# serial_extender.net
KiCad netlist of a schematic drawn in EAGLE
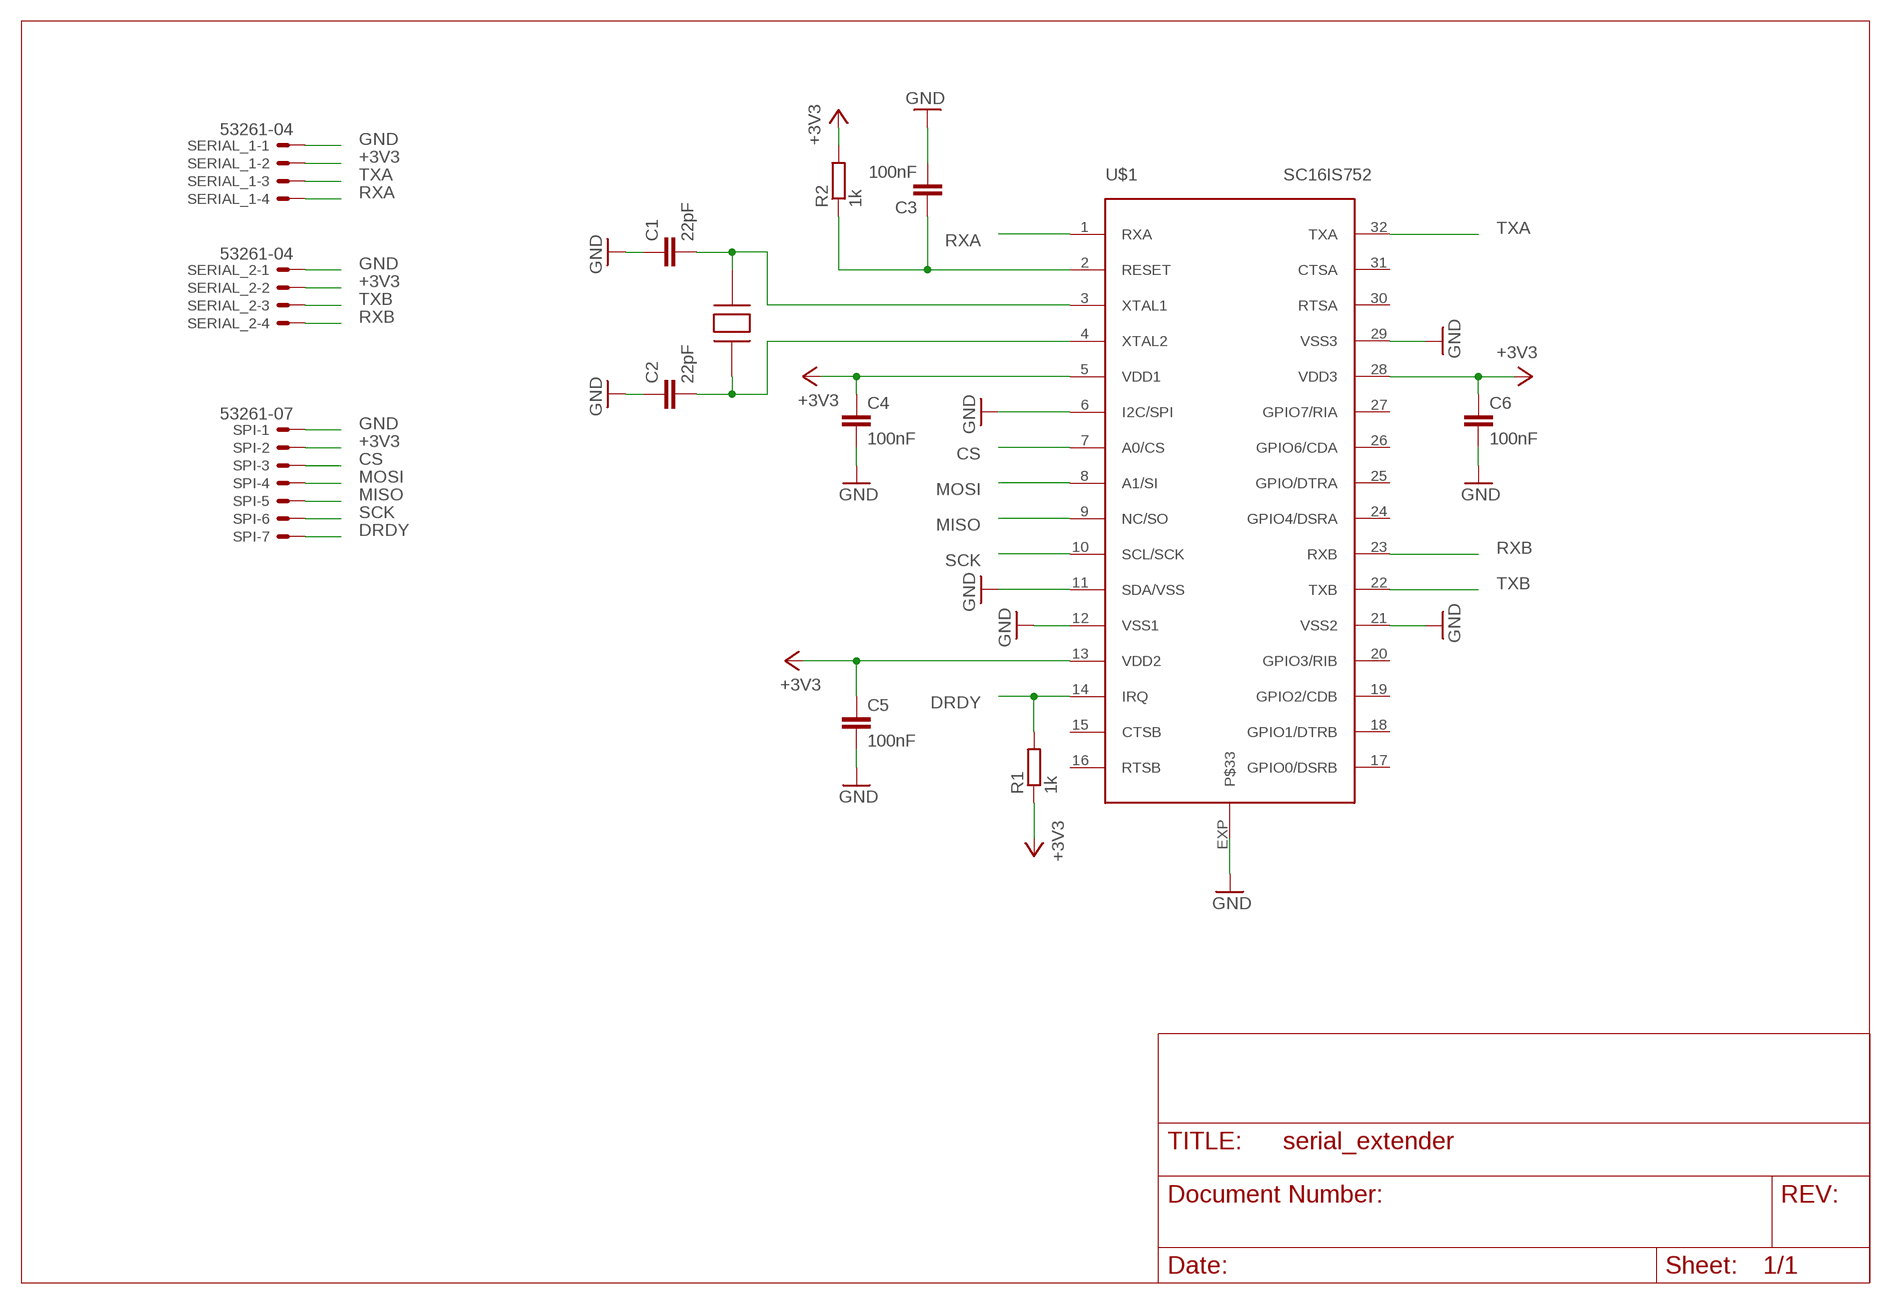
[diagram p0: schematic, sheet 1]

(export (version "E")
  (design (tool "Eeschema 10.0.6"))
  (components
    (comp (ref "C1")
      (value "22pF")
      (footprint "eagle-import:C0603K")
      (libsource (lib "eagle-import") (part "C-EUC0603K"))
    )
    (comp (ref "C2")
      (value "22pF")
      (footprint "eagle-import:C0603K")
      (libsource (lib "eagle-import") (part "C-EUC0603K"))
    )
    (comp (ref "C3")
      (value "100nF")
      (footprint "eagle-import:C0603K")
      (libsource (lib "eagle-import") (part "C-EUC0603K"))
    )
    (comp (ref "C4")
      (value "100nF")
      (footprint "eagle-import:C0603K")
      (libsource (lib "eagle-import") (part "C-EUC0603K"))
    )
    (comp (ref "C5")
      (value "100nF")
      (footprint "eagle-import:C0603K")
      (libsource (lib "eagle-import") (part "C-EUC0603K"))
    )
    (comp (ref "C6")
      (value "100nF")
      (footprint "eagle-import:C0603K")
      (libsource (lib "eagle-import") (part "C-EUC0603K"))
    )
    (comp (ref "R1")
      (value "1k")
      (footprint "eagle-import:R0603")
      (libsource (lib "eagle-import") (part "R-EU_R0603"))
    )
    (comp (ref "R2")
      (value "1k")
      (footprint "eagle-import:R0603")
      (libsource (lib "eagle-import") (part "R-EU_R0603"))
    )
    (comp (ref "SERIAL_1")
      (value "53261-04")
      (footprint "eagle-import:53261-04")
      (libsource (lib "eagle-import") (part "53?-04261"))
    )
    (comp (ref "SERIAL_2")
      (value "53261-04")
      (footprint "eagle-import:53261-04")
      (libsource (lib "eagle-import") (part "53?-04261"))
    )
    (comp (ref "SPI")
      (value "53261-07")
      (footprint "eagle-import:53261-07")
      (libsource (lib "eagle-import") (part "53?-07261"))
    )
    (comp (ref "U$1")
      (value "SC16IS752")
      (footprint "eagle-import:HVQFN32")
      (libsource (lib "eagle-import") (part "SC16IS752"))
    )
    (comp (ref "U$2")
      (value "CRYSTAL_CTS")
      (footprint "eagle-import:CTS_CRYSTAL")
      (libsource (lib "eagle-import") (part "CRYSTAL_CTS"))
    )
  )
  (nets
    (net (code "1") (name "+3V3") (class "Default")
      (node (ref "C4") (pin "1") (pinfunction "1_1") (pintype "passive"))
      (node (ref "C5") (pin "1") (pinfunction "1_1") (pintype "passive"))
      (node (ref "C6") (pin "1") (pinfunction "1_1") (pintype "passive"))
      (node (ref "R1") (pin "1") (pinfunction "1_1") (pintype "passive"))
      (node (ref "R2") (pin "2") (pinfunction "2_2") (pintype "passive"))
      (node (ref "SERIAL_1") (pin "2") (pinfunction "S_2") (pintype "passive"))
      (node (ref "SERIAL_2") (pin "2") (pinfunction "S_2") (pintype "passive"))
      (node (ref "SPI") (pin "2") (pinfunction "S_2") (pintype "passive"))
      (node (ref "U$1") (pin "13") (pinfunction "VDD2_13") (pintype "bidirectional"))
      (node (ref "U$1") (pin "28") (pinfunction "VDD3_28") (pintype "bidirectional"))
      (node (ref "U$1") (pin "5") (pinfunction "VDD1_5") (pintype "bidirectional"))
    )
    (net (code "2") (name "/CS") (class "Default")
      (node (ref "SPI") (pin "3") (pinfunction "S_3") (pintype "passive"))
      (node (ref "U$1") (pin "7") (pinfunction "A0/CS_7") (pintype "bidirectional"))
    )
    (net (code "3") (name "/DRDY") (class "Default")
      (node (ref "R1") (pin "2") (pinfunction "2_2") (pintype "passive"))
      (node (ref "SPI") (pin "7") (pinfunction "S_7") (pintype "passive"))
      (node (ref "U$1") (pin "14") (pinfunction "IRQ_14") (pintype "bidirectional"))
    )
    (net (code "4") (name "/MISO") (class "Default")
      (node (ref "SPI") (pin "5") (pinfunction "S_5") (pintype "passive"))
      (node (ref "U$1") (pin "9") (pinfunction "NC/SO_9") (pintype "bidirectional"))
    )
    (net (code "5") (name "/MOSI") (class "Default")
      (node (ref "SPI") (pin "4") (pinfunction "S_4") (pintype "passive"))
      (node (ref "U$1") (pin "8") (pinfunction "A1/SI_8") (pintype "bidirectional"))
    )
    (net (code "6") (name "/RXA") (class "Default")
      (node (ref "SERIAL_1") (pin "4") (pinfunction "S_4") (pintype "passive"))
      (node (ref "U$1") (pin "1") (pinfunction "RXA_1") (pintype "bidirectional"))
    )
    (net (code "7") (name "/RXB") (class "Default")
      (node (ref "SERIAL_2") (pin "4") (pinfunction "S_4") (pintype "passive"))
      (node (ref "U$1") (pin "23") (pinfunction "RXB_23") (pintype "bidirectional"))
    )
    (net (code "8") (name "/SCK") (class "Default")
      (node (ref "SPI") (pin "6") (pinfunction "S_6") (pintype "passive"))
      (node (ref "U$1") (pin "10") (pinfunction "SCL/SCK_10") (pintype "bidirectional"))
    )
    (net (code "9") (name "/TXA") (class "Default")
      (node (ref "SERIAL_1") (pin "3") (pinfunction "S_3") (pintype "passive"))
      (node (ref "U$1") (pin "32") (pinfunction "TXA_32") (pintype "bidirectional"))
    )
    (net (code "10") (name "/TXB") (class "Default")
      (node (ref "SERIAL_2") (pin "3") (pinfunction "S_3") (pintype "passive"))
      (node (ref "U$1") (pin "22") (pinfunction "TXB_22") (pintype "bidirectional"))
    )
    (net (code "11") (name "GND") (class "Default")
      (node (ref "C1") (pin "1") (pinfunction "1_1") (pintype "passive"))
      (node (ref "C2") (pin "1") (pinfunction "1_1") (pintype "passive"))
      (node (ref "C3") (pin "2") (pinfunction "2_2") (pintype "passive"))
      (node (ref "C4") (pin "2") (pinfunction "2_2") (pintype "passive"))
      (node (ref "C5") (pin "2") (pinfunction "2_2") (pintype "passive"))
      (node (ref "C6") (pin "2") (pinfunction "2_2") (pintype "passive"))
      (node (ref "SERIAL_1") (pin "1") (pinfunction "S_1") (pintype "passive"))
      (node (ref "SERIAL_2") (pin "1") (pinfunction "S_1") (pintype "passive"))
      (node (ref "SPI") (pin "1") (pinfunction "S_1") (pintype "passive"))
      (node (ref "U$1") (pin "11") (pinfunction "SDA/VSS_11") (pintype "bidirectional"))
      (node (ref "U$1") (pin "12") (pinfunction "VSS1_12") (pintype "bidirectional"))
      (node (ref "U$1") (pin "21") (pinfunction "VSS2_21") (pintype "bidirectional"))
      (node (ref "U$1") (pin "29") (pinfunction "VSS3_29") (pintype "bidirectional"))
      (node (ref "U$1") (pin "6") (pinfunction "I2C/SPI_6") (pintype "bidirectional"))
      (node (ref "U$1") (pin "EXP") (pinfunction "P$33_EXP") (pintype "bidirectional"))
    )
    (net (code "12") (name "Net-(U$1-RESET)") (class "Default")
      (node (ref "C3") (pin "1") (pinfunction "1_1") (pintype "passive"))
      (node (ref "R2") (pin "1") (pinfunction "1_1") (pintype "passive"))
      (node (ref "U$1") (pin "2") (pinfunction "RESET_2") (pintype "bidirectional"))
    )
    (net (code "13") (name "Net-(U$1-XTAL1)") (class "Default")
      (node (ref "C1") (pin "2") (pinfunction "2_2") (pintype "passive"))
      (node (ref "U$1") (pin "3") (pinfunction "XTAL1_3") (pintype "bidirectional"))
      (node (ref "U$2") (pin "P$3") (pinfunction "P$2_P$3") (pintype "bidirectional"))
    )
    (net (code "14") (name "Net-(U$1-XTAL2)") (class "Default")
      (node (ref "C2") (pin "2") (pinfunction "2_2") (pintype "passive"))
      (node (ref "U$1") (pin "4") (pinfunction "XTAL2_4") (pintype "bidirectional"))
      (node (ref "U$2") (pin "P$1") (pinfunction "P$1_P$1") (pintype "bidirectional"))
    )
    (net (code "15") (name "unconnected-(U$1-CTSA-Pad31)") (class "Default")
      (node (ref "U$1") (pin "31") (pinfunction "CTSA_31") (pintype "bidirectional"))
    )
    (net (code "16") (name "unconnected-(U$1-CTSB-Pad15)") (class "Default")
      (node (ref "U$1") (pin "15") (pinfunction "CTSB_15") (pintype "bidirectional"))
    )
    (net (code "17") (name "unconnected-(U$1-GPIO0{slash}DSRB-Pad17)") (class "Default")
      (node (ref "U$1") (pin "17") (pinfunction "GPIO0/DSRB_17") (pintype "bidirectional"))
    )
    (net (code "18") (name "unconnected-(U$1-GPIO1{slash}DTRB-Pad18)") (class "Default")
      (node (ref "U$1") (pin "18") (pinfunction "GPIO1/DTRB_18") (pintype "bidirectional"))
    )
    (net (code "19") (name "unconnected-(U$1-GPIO2{slash}CDB-Pad19)") (class "Default")
      (node (ref "U$1") (pin "19") (pinfunction "GPIO2/CDB_19") (pintype "bidirectional"))
    )
    (net (code "20") (name "unconnected-(U$1-GPIO3{slash}RIB-Pad20)") (class "Default")
      (node (ref "U$1") (pin "20") (pinfunction "GPIO3/RIB_20") (pintype "bidirectional"))
    )
    (net (code "21") (name "unconnected-(U$1-GPIO4{slash}DSRA-Pad24)") (class "Default")
      (node (ref "U$1") (pin "24") (pinfunction "GPIO4/DSRA_24") (pintype "bidirectional"))
    )
    (net (code "22") (name "unconnected-(U$1-GPIO6{slash}CDA-Pad26)") (class "Default")
      (node (ref "U$1") (pin "26") (pinfunction "GPIO6/CDA_26") (pintype "bidirectional"))
    )
    (net (code "23") (name "unconnected-(U$1-GPIO7{slash}RIA-Pad27)") (class "Default")
      (node (ref "U$1") (pin "27") (pinfunction "GPIO7/RIA_27") (pintype "bidirectional"))
    )
    (net (code "24") (name "unconnected-(U$1-GPIO{slash}DTRA-Pad25)") (class "Default")
      (node (ref "U$1") (pin "25") (pinfunction "GPIO/DTRA_25") (pintype "bidirectional"))
    )
    (net (code "25") (name "unconnected-(U$1-RTSA-Pad30)") (class "Default")
      (node (ref "U$1") (pin "30") (pinfunction "RTSA_30") (pintype "bidirectional"))
    )
    (net (code "26") (name "unconnected-(U$1-RTSB-Pad16)") (class "Default")
      (node (ref "U$1") (pin "16") (pinfunction "RTSB_16") (pintype "bidirectional"))
    )
  )
)
